# mothership_compact_0_42.net
KiCad netlist of a schematic drawn in EAGLE
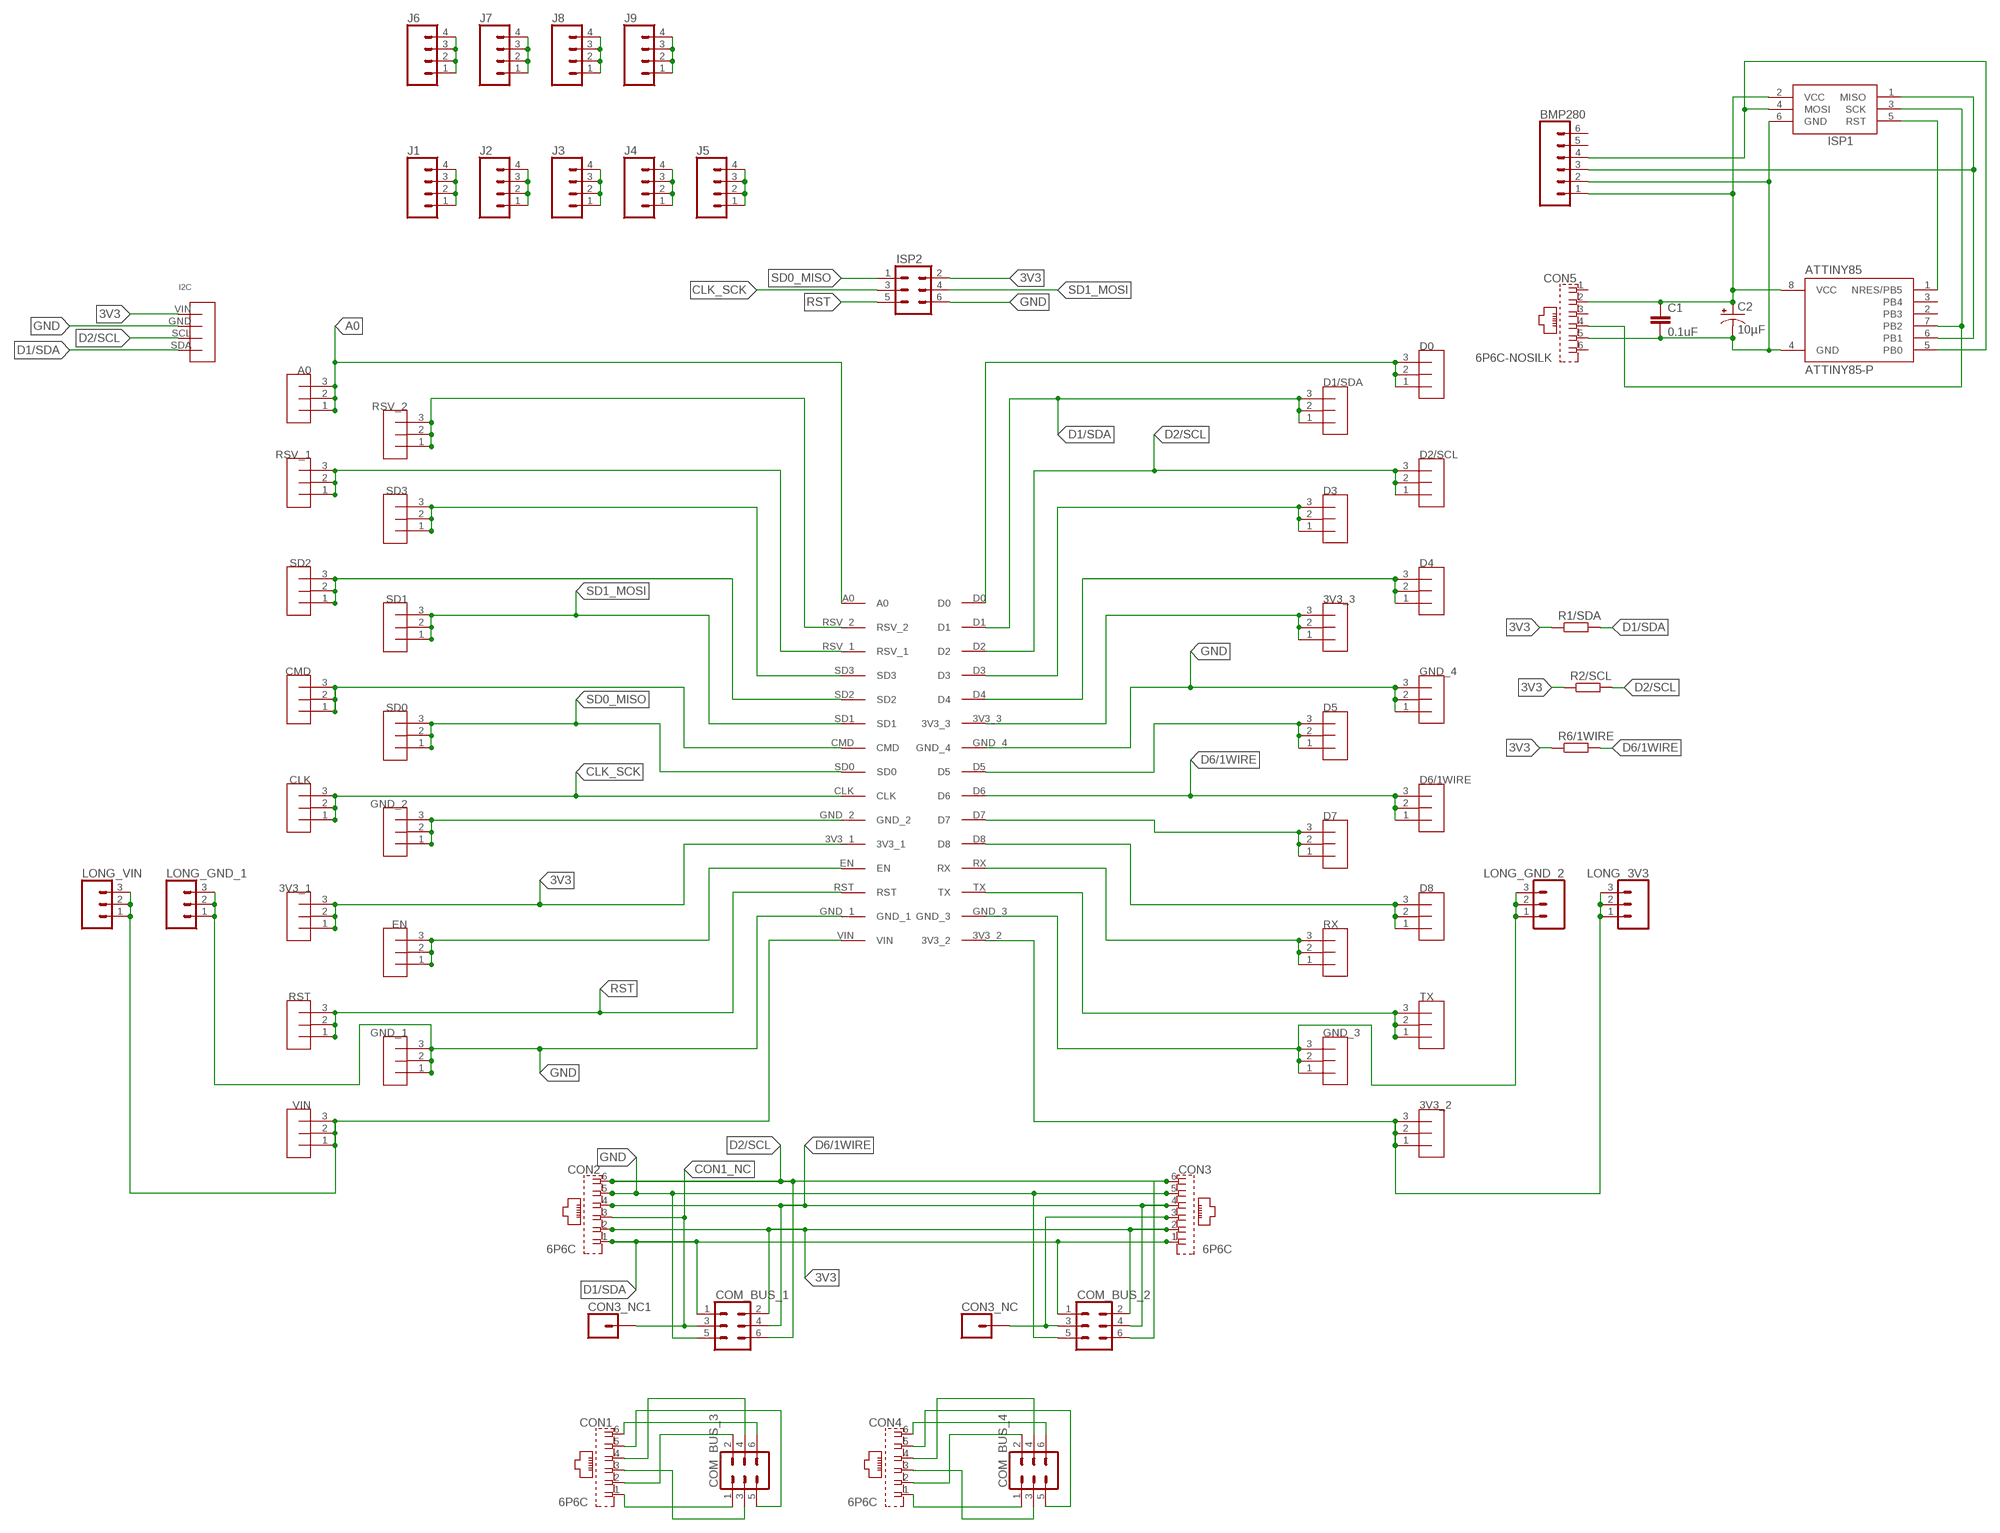
[diagram p0: schematic, sheet 1]

(export (version "E")
  (design (tool "Eeschema 10.0.6"))
  (components
    (comp (ref "3V3_1")
      (value "JUMPERS")
      (footprint "eagle-import:3PIN")
      (libsource (lib "eagle-import") (part "JUMPERS"))
    )
    (comp (ref "3V3_2")
      (value "JUMPERS")
      (footprint "eagle-import:3PIN")
      (libsource (lib "eagle-import") (part "JUMPERS"))
    )
    (comp (ref "3V3_3")
      (value "JUMPERS")
      (footprint "eagle-import:3PIN")
      (libsource (lib "eagle-import") (part "JUMPERS"))
    )
    (comp (ref "A0")
      (value "JUMPERS")
      (footprint "eagle-import:3PIN")
      (libsource (lib "eagle-import") (part "JUMPERS"))
    )
    (comp (ref "ATTINY85")
      (value "ATTINY85-P")
      (footprint "eagle-import:PDIP08_300MIL")
      (libsource (lib "eagle-import") (part "ATTINY85P-"))
    )
    (comp (ref "BMP280")
      (value "CONN_06NO_SILK_NO_POP")
      (footprint "eagle-import:1X06_NO_SILK")
      (libsource (lib "eagle-import") (part "CONN_06NO_SILK_NO_POP"))
    )
    (comp (ref "C1")
      (value "0.1uF")
      (footprint "eagle-import:C050-045X075")
      (libsource (lib "eagle-import") (part "C-EU050-045X075"))
    )
    (comp (ref "C2")
      (value "10µF")
      (footprint "eagle-import:E2,5-5")
      (libsource (lib "eagle-import") (part "CPOL-USE2.5-5"))
    )
    (comp (ref "CLK")
      (value "JUMPERS")
      (footprint "eagle-import:3PIN")
      (libsource (lib "eagle-import") (part "JUMPERS"))
    )
    (comp (ref "CMD")
      (value "JUMPERS")
      (footprint "eagle-import:3PIN")
      (libsource (lib "eagle-import") (part "JUMPERS"))
    )
    (comp (ref "COM_BUS_1")
      (value "CONN_03X2NO_SILK")
      (footprint "eagle-import:2X3-NS")
      (libsource (lib "eagle-import") (part "CONN_03X2NO_SILK"))
    )
    (comp (ref "COM_BUS_2")
      (value "CONN_03X2NO_SILK")
      (footprint "eagle-import:2X3-NS")
      (libsource (lib "eagle-import") (part "CONN_03X2NO_SILK"))
    )
    (comp (ref "COM_BUS_3")
      (value "CONN_03X2NO_SILK")
      (footprint "eagle-import:2X3-NS")
      (libsource (lib "eagle-import") (part "CONN_03X2NO_SILK"))
    )
    (comp (ref "COM_BUS_4")
      (value "CONN_03X2NO_SILK")
      (footprint "eagle-import:2X3-NS")
      (libsource (lib "eagle-import") (part "CONN_03X2NO_SILK"))
    )
    (comp (ref "CON1")
      (value "6P6C")
      (footprint "eagle-import:RJ11-6P6C-NOSHIELD")
      (libsource (lib "eagle-import") (part "6P6C"))
    )
    (comp (ref "CON2")
      (value "6P6C")
      (footprint "eagle-import:RJ11-6P6C-NOSHIELD")
      (libsource (lib "eagle-import") (part "6P6C"))
    )
    (comp (ref "CON3")
      (value "6P6C")
      (footprint "eagle-import:RJ11-6P6C-NOSHIELD")
      (libsource (lib "eagle-import") (part "6P6C"))
    )
    (comp (ref "CON3_NC")
      (value "CONN_01PTH_NO_SILK_YES_STOP")
      (footprint "eagle-import:1X01_NO_SILK")
      (libsource (lib "eagle-import") (part "CONN_01PTH_NO_SILK_YES_STOP"))
    )
    (comp (ref "CON3_NC1")
      (value "CONN_01PTH_NO_SILK_YES_STOP")
      (footprint "eagle-import:1X01_NO_SILK")
      (libsource (lib "eagle-import") (part "CONN_01PTH_NO_SILK_YES_STOP"))
    )
    (comp (ref "CON4")
      (value "6P6C")
      (footprint "eagle-import:RJ11-6P6C-NOSHIELD")
      (libsource (lib "eagle-import") (part "6P6C"))
    )
    (comp (ref "CON5")
      (value "6P6C-NOSILK")
      (footprint "eagle-import:RJ11-6P6C-NOSHIELD-NOSILK")
      (libsource (lib "eagle-import") (part "6P6C-NOSILK"))
    )
    (comp (ref "D0")
      (value "JUMPERS")
      (footprint "eagle-import:3PIN")
      (libsource (lib "eagle-import") (part "JUMPERS"))
    )
    (comp (ref "D1/SDA")
      (value "JUMPERS")
      (footprint "eagle-import:3PIN")
      (libsource (lib "eagle-import") (part "JUMPERS"))
    )
    (comp (ref "D2/SCL")
      (value "JUMPERS")
      (footprint "eagle-import:3PIN")
      (libsource (lib "eagle-import") (part "JUMPERS"))
    )
    (comp (ref "D3")
      (value "JUMPERS")
      (footprint "eagle-import:3PIN")
      (libsource (lib "eagle-import") (part "JUMPERS"))
    )
    (comp (ref "D4")
      (value "JUMPERS")
      (footprint "eagle-import:3PIN")
      (libsource (lib "eagle-import") (part "JUMPERS"))
    )
    (comp (ref "D5")
      (value "JUMPERS")
      (footprint "eagle-import:3PIN")
      (libsource (lib "eagle-import") (part "JUMPERS"))
    )
    (comp (ref "D6/1WIRE")
      (value "JUMPERS")
      (footprint "eagle-import:3PIN")
      (libsource (lib "eagle-import") (part "JUMPERS"))
    )
    (comp (ref "D7")
      (value "JUMPERS")
      (footprint "eagle-import:3PIN")
      (libsource (lib "eagle-import") (part "JUMPERS"))
    )
    (comp (ref "D8")
      (value "JUMPERS")
      (footprint "eagle-import:3PIN")
      (libsource (lib "eagle-import") (part "JUMPERS"))
    )
    (comp (ref "EN")
      (value "JUMPERS")
      (footprint "eagle-import:3PIN")
      (libsource (lib "eagle-import") (part "JUMPERS"))
    )
    (comp (ref "GND_1")
      (value "JUMPERS")
      (footprint "eagle-import:3PIN")
      (libsource (lib "eagle-import") (part "JUMPERS"))
    )
    (comp (ref "GND_2")
      (value "JUMPERS")
      (footprint "eagle-import:3PIN")
      (libsource (lib "eagle-import") (part "JUMPERS"))
    )
    (comp (ref "GND_3")
      (value "JUMPERS")
      (footprint "eagle-import:3PIN")
      (libsource (lib "eagle-import") (part "JUMPERS"))
    )
    (comp (ref "GND_4")
      (value "JUMPERS")
      (footprint "eagle-import:3PIN")
      (libsource (lib "eagle-import") (part "JUMPERS"))
    )
    (comp (ref "ISP1")
      (value "AVRISP-6")
      (footprint "eagle-import:AVRISP")
      (libsource (lib "eagle-import") (part "AVRISP-6"))
    )
    (comp (ref "ISP2")
      (value "CONN_03X2NO_SILK")
      (footprint "eagle-import:2X3-NS")
      (libsource (lib "eagle-import") (part "CONN_03X2NO_SILK"))
    )
    (comp (ref "J1")
      (value "CONN_041X04_NO_SILK")
      (footprint "eagle-import:1X04_NO_SILK")
      (libsource (lib "eagle-import") (part "CONN_041X04_NO_SILK"))
    )
    (comp (ref "J2")
      (value "CONN_041X04_NO_SILK")
      (footprint "eagle-import:1X04_NO_SILK")
      (libsource (lib "eagle-import") (part "CONN_041X04_NO_SILK"))
    )
    (comp (ref "J3")
      (value "CONN_041X04_NO_SILK")
      (footprint "eagle-import:1X04_NO_SILK")
      (libsource (lib "eagle-import") (part "CONN_041X04_NO_SILK"))
    )
    (comp (ref "J4")
      (value "CONN_041X04_NO_SILK")
      (footprint "eagle-import:1X04_NO_SILK")
      (libsource (lib "eagle-import") (part "CONN_041X04_NO_SILK"))
    )
    (comp (ref "J5")
      (value "CONN_041X04_NO_SILK")
      (footprint "eagle-import:1X04_NO_SILK")
      (libsource (lib "eagle-import") (part "CONN_041X04_NO_SILK"))
    )
    (comp (ref "J6")
      (value "CONN_041X04_NO_SILK")
      (footprint "eagle-import:1X04_NO_SILK")
      (libsource (lib "eagle-import") (part "CONN_041X04_NO_SILK"))
    )
    (comp (ref "J7")
      (value "CONN_041X04_NO_SILK")
      (footprint "eagle-import:1X04_NO_SILK")
      (libsource (lib "eagle-import") (part "CONN_041X04_NO_SILK"))
    )
    (comp (ref "J8")
      (value "CONN_041X04_NO_SILK")
      (footprint "eagle-import:1X04_NO_SILK")
      (libsource (lib "eagle-import") (part "CONN_041X04_NO_SILK"))
    )
    (comp (ref "J9")
      (value "CONN_041X04_NO_SILK")
      (footprint "eagle-import:1X04_NO_SILK")
      (libsource (lib "eagle-import") (part "CONN_041X04_NO_SILK"))
    )
    (comp (ref "LONG_3V3")
      (value "CONN_03")
      (footprint "eagle-import:1X03")
      (libsource (lib "eagle-import") (part "CONN_03"))
    )
    (comp (ref "LONG_GND_1")
      (value "CONN_03")
      (footprint "eagle-import:1X03")
      (libsource (lib "eagle-import") (part "CONN_03"))
    )
    (comp (ref "LONG_GND_2")
      (value "CONN_03")
      (footprint "eagle-import:1X03")
      (libsource (lib "eagle-import") (part "CONN_03"))
    )
    (comp (ref "LONG_VIN")
      (value "CONN_03")
      (footprint "eagle-import:1X03")
      (libsource (lib "eagle-import") (part "CONN_03"))
    )
    (comp (ref "R1/SDA")
      (value "R-EU_0207/10")
      (footprint "eagle-import:0207_10")
      (libsource (lib "eagle-import") (part "R-EU_0207/10"))
    )
    (comp (ref "R2/SCL")
      (value "R-EU_0207/10")
      (footprint "eagle-import:0207_10")
      (libsource (lib "eagle-import") (part "R-EU_0207/10"))
    )
    (comp (ref "R6/1WIRE")
      (value "R-EU_0207/10")
      (footprint "eagle-import:0207_10")
      (libsource (lib "eagle-import") (part "R-EU_0207/10"))
    )
    (comp (ref "RST")
      (value "JUMPERS")
      (footprint "eagle-import:3PIN")
      (libsource (lib "eagle-import") (part "JUMPERS"))
    )
    (comp (ref "RSV_1")
      (value "JUMPERS")
      (footprint "eagle-import:3PIN")
      (libsource (lib "eagle-import") (part "JUMPERS"))
    )
    (comp (ref "RSV_2")
      (value "JUMPERS")
      (footprint "eagle-import:3PIN")
      (libsource (lib "eagle-import") (part "JUMPERS"))
    )
    (comp (ref "RX")
      (value "JUMPERS")
      (footprint "eagle-import:3PIN")
      (libsource (lib "eagle-import") (part "JUMPERS"))
    )
    (comp (ref "SD0")
      (value "JUMPERS")
      (footprint "eagle-import:3PIN")
      (libsource (lib "eagle-import") (part "JUMPERS"))
    )
    (comp (ref "SD1")
      (value "JUMPERS")
      (footprint "eagle-import:3PIN")
      (libsource (lib "eagle-import") (part "JUMPERS"))
    )
    (comp (ref "SD2")
      (value "JUMPERS")
      (footprint "eagle-import:3PIN")
      (libsource (lib "eagle-import") (part "JUMPERS"))
    )
    (comp (ref "SD3")
      (value "JUMPERS")
      (footprint "eagle-import:3PIN")
      (libsource (lib "eagle-import") (part "JUMPERS"))
    )
    (comp (ref "TX")
      (value "JUMPERS")
      (footprint "eagle-import:3PIN")
      (libsource (lib "eagle-import") (part "JUMPERS"))
    )
    (comp (ref "U$1")
      (value "NODEMCU")
      (footprint "eagle-import:NODEMCU")
      (libsource (lib "eagle-import") (part "NODEMCU"))
    )
    (comp (ref "U$2")
      (value "I2CJUMPER")
      (footprint "eagle-import:4PIN,NAMED")
      (libsource (lib "eagle-import") (part "I2CJUMPER"))
    )
    (comp (ref "VIN")
      (value "JUMPERS")
      (footprint "eagle-import:3PIN")
      (libsource (lib "eagle-import") (part "JUMPERS"))
    )
  )
  (nets
    (net (code "1") (name "3V3") (class "Default")
      (node (ref "3V3_1") (pin "1") (pinfunction "P$1_1") (pintype "bidirectional"))
      (node (ref "3V3_1") (pin "2") (pinfunction "P$2_2") (pintype "bidirectional"))
      (node (ref "3V3_1") (pin "3") (pinfunction "P$3_3") (pintype "bidirectional"))
      (node (ref "3V3_2") (pin "1") (pinfunction "P$1_1") (pintype "bidirectional"))
      (node (ref "3V3_2") (pin "2") (pinfunction "P$2_2") (pintype "bidirectional"))
      (node (ref "3V3_2") (pin "3") (pinfunction "P$3_3") (pintype "bidirectional"))
      (node (ref "3V3_3") (pin "1") (pinfunction "P$1_1") (pintype "bidirectional"))
      (node (ref "3V3_3") (pin "2") (pinfunction "P$2_2") (pintype "bidirectional"))
      (node (ref "3V3_3") (pin "3") (pinfunction "P$3_3") (pintype "bidirectional"))
      (node (ref "COM_BUS_1") (pin "2") (pinfunction "2_2") (pintype "bidirectional"))
      (node (ref "COM_BUS_2") (pin "2") (pinfunction "2_2") (pintype "bidirectional"))
      (node (ref "CON2") (pin "2") (pinfunction "5_2") (pintype "passive"))
      (node (ref "CON3") (pin "2") (pinfunction "5_2") (pintype "passive"))
      (node (ref "ISP2") (pin "2") (pinfunction "2_2") (pintype "bidirectional"))
      (node (ref "LONG_3V3") (pin "1") (pinfunction "1_1") (pintype "passive"))
      (node (ref "LONG_3V3") (pin "2") (pinfunction "2_2") (pintype "passive"))
      (node (ref "LONG_3V3") (pin "3") (pinfunction "3_3") (pintype "passive"))
      (node (ref "R1/SDA") (pin "1") (pinfunction "1_1") (pintype "passive"))
      (node (ref "R2/SCL") (pin "1") (pinfunction "1_1") (pintype "passive"))
      (node (ref "R6/1WIRE") (pin "1") (pinfunction "1_1") (pintype "passive"))
      (node (ref "U$1") (pin "3V3_1") (pinfunction "3V3_1_3V3_1") (pintype "bidirectional"))
      (node (ref "U$1") (pin "3V3_2") (pinfunction "3V3_2_3V3_2") (pintype "bidirectional"))
      (node (ref "U$1") (pin "3V3_3") (pinfunction "3V3_3_3V3_3") (pintype "bidirectional"))
      (node (ref "U$2") (pin "VIN") (pinfunction "VIN_VIN") (pintype "bidirectional"))
    )
    (net (code "2") (name "A0") (class "Default")
      (node (ref "A0") (pin "1") (pinfunction "P$1_1") (pintype "bidirectional"))
      (node (ref "A0") (pin "2") (pinfunction "P$2_2") (pintype "bidirectional"))
      (node (ref "A0") (pin "3") (pinfunction "P$3_3") (pintype "bidirectional"))
      (node (ref "U$1") (pin "A0") (pinfunction "A0_A0") (pintype "bidirectional"))
    )
    (net (code "3") (name "CLK_SCK") (class "Default")
      (node (ref "CLK") (pin "1") (pinfunction "P$1_1") (pintype "bidirectional"))
      (node (ref "CLK") (pin "2") (pinfunction "P$2_2") (pintype "bidirectional"))
      (node (ref "CLK") (pin "3") (pinfunction "P$3_3") (pintype "bidirectional"))
      (node (ref "ISP2") (pin "3") (pinfunction "3_3") (pintype "bidirectional"))
      (node (ref "U$1") (pin "CLK") (pinfunction "CLK_CLK") (pintype "bidirectional"))
    )
    (net (code "4") (name "CON1_NC") (class "Default")
      (node (ref "COM_BUS_1") (pin "3") (pinfunction "3_3") (pintype "bidirectional"))
      (node (ref "CON2") (pin "3") (pinfunction "4_3") (pintype "passive"))
      (node (ref "CON3_NC1") (pin "1") (pinfunction "1_1") (pintype "passive"))
    )
    (net (code "5") (name "D1{slash}SDA") (class "Default")
      (node (ref "COM_BUS_1") (pin "1") (pinfunction "1_1") (pintype "bidirectional"))
      (node (ref "COM_BUS_2") (pin "1") (pinfunction "1_1") (pintype "bidirectional"))
      (node (ref "CON2") (pin "1") (pinfunction "6_1") (pintype "passive"))
      (node (ref "CON3") (pin "1") (pinfunction "6_1") (pintype "passive"))
      (node (ref "D1/SDA") (pin "1") (pinfunction "P$1_1") (pintype "bidirectional"))
      (node (ref "D1/SDA") (pin "2") (pinfunction "P$2_2") (pintype "bidirectional"))
      (node (ref "D1/SDA") (pin "3") (pinfunction "P$3_3") (pintype "bidirectional"))
      (node (ref "R1/SDA") (pin "2") (pinfunction "2_2") (pintype "passive"))
      (node (ref "U$1") (pin "D1") (pinfunction "D1_D1") (pintype "bidirectional"))
      (node (ref "U$2") (pin "SDA") (pinfunction "SDA_SDA") (pintype "bidirectional"))
    )
    (net (code "6") (name "D2{slash}SCL") (class "Default")
      (node (ref "COM_BUS_1") (pin "6") (pinfunction "6_6") (pintype "bidirectional"))
      (node (ref "COM_BUS_2") (pin "6") (pinfunction "6_6") (pintype "bidirectional"))
      (node (ref "CON2") (pin "6") (pinfunction "1_6") (pintype "passive"))
      (node (ref "CON3") (pin "6") (pinfunction "1_6") (pintype "passive"))
      (node (ref "D2/SCL") (pin "1") (pinfunction "P$1_1") (pintype "bidirectional"))
      (node (ref "D2/SCL") (pin "2") (pinfunction "P$2_2") (pintype "bidirectional"))
      (node (ref "D2/SCL") (pin "3") (pinfunction "P$3_3") (pintype "bidirectional"))
      (node (ref "R2/SCL") (pin "2") (pinfunction "2_2") (pintype "passive"))
      (node (ref "U$1") (pin "D2") (pinfunction "D2_D2") (pintype "bidirectional"))
      (node (ref "U$2") (pin "SCL") (pinfunction "SCL_SCL") (pintype "bidirectional"))
    )
    (net (code "7") (name "D6{slash}1WIRE") (class "Default")
      (node (ref "COM_BUS_1") (pin "4") (pinfunction "4_4") (pintype "bidirectional"))
      (node (ref "COM_BUS_2") (pin "4") (pinfunction "4_4") (pintype "bidirectional"))
      (node (ref "CON2") (pin "4") (pinfunction "3_4") (pintype "passive"))
      (node (ref "CON3") (pin "4") (pinfunction "3_4") (pintype "passive"))
      (node (ref "D6/1WIRE") (pin "1") (pinfunction "P$1_1") (pintype "bidirectional"))
      (node (ref "D6/1WIRE") (pin "2") (pinfunction "P$2_2") (pintype "bidirectional"))
      (node (ref "D6/1WIRE") (pin "3") (pinfunction "P$3_3") (pintype "bidirectional"))
      (node (ref "R6/1WIRE") (pin "2") (pinfunction "2_2") (pintype "passive"))
      (node (ref "U$1") (pin "D6") (pinfunction "D6_D6") (pintype "bidirectional"))
    )
    (net (code "8") (name "GND") (class "Default")
      (node (ref "COM_BUS_1") (pin "5") (pinfunction "5_5") (pintype "bidirectional"))
      (node (ref "COM_BUS_2") (pin "5") (pinfunction "5_5") (pintype "bidirectional"))
      (node (ref "CON2") (pin "5") (pinfunction "2_5") (pintype "passive"))
      (node (ref "CON3") (pin "5") (pinfunction "2_5") (pintype "passive"))
      (node (ref "GND_1") (pin "1") (pinfunction "P$1_1") (pintype "bidirectional"))
      (node (ref "GND_1") (pin "2") (pinfunction "P$2_2") (pintype "bidirectional"))
      (node (ref "GND_1") (pin "3") (pinfunction "P$3_3") (pintype "bidirectional"))
      (node (ref "GND_2") (pin "1") (pinfunction "P$1_1") (pintype "bidirectional"))
      (node (ref "GND_2") (pin "2") (pinfunction "P$2_2") (pintype "bidirectional"))
      (node (ref "GND_2") (pin "3") (pinfunction "P$3_3") (pintype "bidirectional"))
      (node (ref "GND_3") (pin "1") (pinfunction "P$1_1") (pintype "bidirectional"))
      (node (ref "GND_3") (pin "2") (pinfunction "P$2_2") (pintype "bidirectional"))
      (node (ref "GND_3") (pin "3") (pinfunction "P$3_3") (pintype "bidirectional"))
      (node (ref "GND_4") (pin "1") (pinfunction "P$1_1") (pintype "bidirectional"))
      (node (ref "GND_4") (pin "2") (pinfunction "P$2_2") (pintype "bidirectional"))
      (node (ref "GND_4") (pin "3") (pinfunction "P$3_3") (pintype "bidirectional"))
      (node (ref "ISP2") (pin "6") (pinfunction "6_6") (pintype "bidirectional"))
      (node (ref "LONG_GND_1") (pin "1") (pinfunction "1_1") (pintype "passive"))
      (node (ref "LONG_GND_1") (pin "2") (pinfunction "2_2") (pintype "passive"))
      (node (ref "LONG_GND_1") (pin "3") (pinfunction "3_3") (pintype "passive"))
      (node (ref "LONG_GND_2") (pin "1") (pinfunction "1_1") (pintype "passive"))
      (node (ref "LONG_GND_2") (pin "2") (pinfunction "2_2") (pintype "passive"))
      (node (ref "LONG_GND_2") (pin "3") (pinfunction "3_3") (pintype "passive"))
      (node (ref "U$1") (pin "GND_1") (pinfunction "GND_1_GND_1") (pintype "bidirectional"))
      (node (ref "U$1") (pin "GND_2") (pinfunction "GND_2_GND_2") (pintype "bidirectional"))
      (node (ref "U$1") (pin "GND_3") (pinfunction "GND_3_GND_3") (pintype "bidirectional"))
      (node (ref "U$1") (pin "GND_4") (pinfunction "GND_4_GND_4") (pintype "bidirectional"))
      (node (ref "U$2") (pin "GND") (pinfunction "GND_GND") (pintype "bidirectional"))
    )
    (net (code "9") (name "Net-(ATTINY85-GND)") (class "Default")
      (node (ref "ATTINY85") (pin "4") (pinfunction "GND_4") (pintype "power_in"))
      (node (ref "BMP280") (pin "2") (pinfunction "2_2") (pintype "passive"))
      (node (ref "C1") (pin "2") (pinfunction "2_2") (pintype "passive"))
      (node (ref "C2") (pin "-") (pinfunction "-_-") (pintype "passive"))
      (node (ref "CON5") (pin "5") (pinfunction "5_5") (pintype "passive"))
      (node (ref "ISP1") (pin "6") (pinfunction "GND_6") (pintype "power_in"))
    )
    (net (code "10") (name "Net-(ATTINY85-NRES{slash}PB5)") (class "Default")
      (node (ref "ATTINY85") (pin "1") (pinfunction "NRES/PB5_1") (pintype "bidirectional"))
      (node (ref "ISP1") (pin "5") (pinfunction "RST_5") (pintype "output"))
    )
    (net (code "11") (name "Net-(ATTINY85-PB0)") (class "Default")
      (node (ref "ATTINY85") (pin "5") (pinfunction "PB0_5") (pintype "bidirectional"))
      (node (ref "BMP280") (pin "4") (pinfunction "4_4") (pintype "passive"))
      (node (ref "ISP1") (pin "4") (pinfunction "MOSI_4") (pintype "output"))
    )
    (net (code "12") (name "Net-(ATTINY85-PB1)") (class "Default")
      (node (ref "ATTINY85") (pin "6") (pinfunction "PB1_6") (pintype "bidirectional"))
      (node (ref "BMP280") (pin "3") (pinfunction "3_3") (pintype "passive"))
      (node (ref "ISP1") (pin "1") (pinfunction "MISO_1") (pintype "input"))
    )
    (net (code "13") (name "Net-(ATTINY85-PB2)") (class "Default")
      (node (ref "ATTINY85") (pin "7") (pinfunction "PB2_7") (pintype "bidirectional"))
      (node (ref "CON5") (pin "4") (pinfunction "4_4") (pintype "passive"))
      (node (ref "ISP1") (pin "3") (pinfunction "SCK_3") (pintype "output"))
    )
    (net (code "14") (name "Net-(ATTINY85-VCC)") (class "Default")
      (node (ref "ATTINY85") (pin "8") (pinfunction "VCC_8") (pintype "power_in"))
      (node (ref "BMP280") (pin "1") (pinfunction "1_1") (pintype "passive"))
      (node (ref "C1") (pin "1") (pinfunction "1_1") (pintype "passive"))
      (node (ref "C2") (pin "+") (pinfunction "+_+") (pintype "passive"))
      (node (ref "CON5") (pin "2") (pinfunction "2_2") (pintype "passive"))
      (node (ref "ISP1") (pin "2") (pinfunction "VCC_2") (pintype "power_in"))
    )
    (net (code "15") (name "Net-(CMD-P$1)") (class "Default")
      (node (ref "CMD") (pin "1") (pinfunction "P$1_1") (pintype "bidirectional"))
      (node (ref "CMD") (pin "2") (pinfunction "P$2_2") (pintype "bidirectional"))
      (node (ref "CMD") (pin "3") (pinfunction "P$3_3") (pintype "bidirectional"))
      (node (ref "U$1") (pin "CMD") (pinfunction "CMD_CMD") (pintype "bidirectional"))
    )
    (net (code "16") (name "Net-(CON1-1)") (class "Default")
      (node (ref "COM_BUS_3") (pin "6") (pinfunction "6_6") (pintype "bidirectional"))
      (node (ref "CON1") (pin "6") (pinfunction "1_6") (pintype "passive"))
    )
    (net (code "17") (name "Net-(CON1-2)") (class "Default")
      (node (ref "COM_BUS_3") (pin "5") (pinfunction "5_5") (pintype "bidirectional"))
      (node (ref "CON1") (pin "5") (pinfunction "2_5") (pintype "passive"))
    )
    (net (code "18") (name "Net-(CON1-3)") (class "Default")
      (node (ref "COM_BUS_3") (pin "4") (pinfunction "4_4") (pintype "bidirectional"))
      (node (ref "CON1") (pin "4") (pinfunction "3_4") (pintype "passive"))
    )
    (net (code "19") (name "Net-(CON1-4)") (class "Default")
      (node (ref "COM_BUS_3") (pin "3") (pinfunction "3_3") (pintype "bidirectional"))
      (node (ref "CON1") (pin "3") (pinfunction "4_3") (pintype "passive"))
    )
    (net (code "20") (name "Net-(CON1-5)") (class "Default")
      (node (ref "COM_BUS_3") (pin "2") (pinfunction "2_2") (pintype "bidirectional"))
      (node (ref "CON1") (pin "2") (pinfunction "5_2") (pintype "passive"))
    )
    (net (code "21") (name "Net-(CON1-6)") (class "Default")
      (node (ref "COM_BUS_3") (pin "1") (pinfunction "1_1") (pintype "bidirectional"))
      (node (ref "CON1") (pin "1") (pinfunction "6_1") (pintype "passive"))
    )
    (net (code "22") (name "Net-(CON3-4)") (class "Default")
      (node (ref "COM_BUS_2") (pin "3") (pinfunction "3_3") (pintype "bidirectional"))
      (node (ref "CON3") (pin "3") (pinfunction "4_3") (pintype "passive"))
      (node (ref "CON3_NC") (pin "1") (pinfunction "1_1") (pintype "passive"))
    )
    (net (code "23") (name "Net-(CON4-1)") (class "Default")
      (node (ref "COM_BUS_4") (pin "6") (pinfunction "6_6") (pintype "bidirectional"))
      (node (ref "CON4") (pin "6") (pinfunction "1_6") (pintype "passive"))
    )
    (net (code "24") (name "Net-(CON4-2)") (class "Default")
      (node (ref "COM_BUS_4") (pin "5") (pinfunction "5_5") (pintype "bidirectional"))
      (node (ref "CON4") (pin "5") (pinfunction "2_5") (pintype "passive"))
    )
    (net (code "25") (name "Net-(CON4-3)") (class "Default")
      (node (ref "COM_BUS_4") (pin "4") (pinfunction "4_4") (pintype "bidirectional"))
      (node (ref "CON4") (pin "4") (pinfunction "3_4") (pintype "passive"))
    )
    (net (code "26") (name "Net-(CON4-4)") (class "Default")
      (node (ref "COM_BUS_4") (pin "3") (pinfunction "3_3") (pintype "bidirectional"))
      (node (ref "CON4") (pin "3") (pinfunction "4_3") (pintype "passive"))
    )
    (net (code "27") (name "Net-(CON4-5)") (class "Default")
      (node (ref "COM_BUS_4") (pin "2") (pinfunction "2_2") (pintype "bidirectional"))
      (node (ref "CON4") (pin "2") (pinfunction "5_2") (pintype "passive"))
    )
    (net (code "28") (name "Net-(CON4-6)") (class "Default")
      (node (ref "COM_BUS_4") (pin "1") (pinfunction "1_1") (pintype "bidirectional"))
      (node (ref "CON4") (pin "1") (pinfunction "6_1") (pintype "passive"))
    )
    (net (code "29") (name "Net-(D0-P$1)") (class "Default")
      (node (ref "D0") (pin "1") (pinfunction "P$1_1") (pintype "bidirectional"))
      (node (ref "D0") (pin "2") (pinfunction "P$2_2") (pintype "bidirectional"))
      (node (ref "D0") (pin "3") (pinfunction "P$3_3") (pintype "bidirectional"))
      (node (ref "U$1") (pin "D0") (pinfunction "D0_D0") (pintype "bidirectional"))
    )
    (net (code "30") (name "Net-(D3-P$1)") (class "Default")
      (node (ref "D3") (pin "1") (pinfunction "P$1_1") (pintype "bidirectional"))
      (node (ref "D3") (pin "2") (pinfunction "P$2_2") (pintype "bidirectional"))
      (node (ref "D3") (pin "3") (pinfunction "P$3_3") (pintype "bidirectional"))
      (node (ref "U$1") (pin "D3") (pinfunction "D3_D3") (pintype "bidirectional"))
    )
    (net (code "31") (name "Net-(D4-P$1)") (class "Default")
      (node (ref "D4") (pin "1") (pinfunction "P$1_1") (pintype "bidirectional"))
      (node (ref "D4") (pin "2") (pinfunction "P$2_2") (pintype "bidirectional"))
      (node (ref "D4") (pin "3") (pinfunction "P$3_3") (pintype "bidirectional"))
      (node (ref "U$1") (pin "D4") (pinfunction "D4_D4") (pintype "bidirectional"))
    )
    (net (code "32") (name "Net-(D5-P$1)") (class "Default")
      (node (ref "D5") (pin "1") (pinfunction "P$1_1") (pintype "bidirectional"))
      (node (ref "D5") (pin "2") (pinfunction "P$2_2") (pintype "bidirectional"))
      (node (ref "D5") (pin "3") (pinfunction "P$3_3") (pintype "bidirectional"))
      (node (ref "U$1") (pin "D5") (pinfunction "D5_D5") (pintype "bidirectional"))
    )
    (net (code "33") (name "Net-(D7-P$1)") (class "Default")
      (node (ref "D7") (pin "1") (pinfunction "P$1_1") (pintype "bidirectional"))
      (node (ref "D7") (pin "2") (pinfunction "P$2_2") (pintype "bidirectional"))
      (node (ref "D7") (pin "3") (pinfunction "P$3_3") (pintype "bidirectional"))
      (node (ref "U$1") (pin "D7") (pinfunction "D7_D7") (pintype "bidirectional"))
    )
    (net (code "34") (name "Net-(D8-P$1)") (class "Default")
      (node (ref "D8") (pin "1") (pinfunction "P$1_1") (pintype "bidirectional"))
      (node (ref "D8") (pin "2") (pinfunction "P$2_2") (pintype "bidirectional"))
      (node (ref "D8") (pin "3") (pinfunction "P$3_3") (pintype "bidirectional"))
      (node (ref "U$1") (pin "D8") (pinfunction "D8_D8") (pintype "bidirectional"))
    )
    (net (code "35") (name "Net-(EN-P$1)") (class "Default")
      (node (ref "EN") (pin "1") (pinfunction "P$1_1") (pintype "bidirectional"))
      (node (ref "EN") (pin "2") (pinfunction "P$2_2") (pintype "bidirectional"))
      (node (ref "EN") (pin "3") (pinfunction "P$3_3") (pintype "bidirectional"))
      (node (ref "U$1") (pin "EN") (pinfunction "EN_EN") (pintype "bidirectional"))
    )
    (net (code "36") (name "Net-(J1-Pad1)") (class "Default")
      (node (ref "J1") (pin "1") (pinfunction "1_1") (pintype "passive"))
      (node (ref "J1") (pin "2") (pinfunction "2_2") (pintype "passive"))
      (node (ref "J1") (pin "3") (pinfunction "3_3") (pintype "passive"))
      (node (ref "J1") (pin "4") (pinfunction "4_4") (pintype "passive"))
    )
    (net (code "37") (name "Net-(J2-Pad1)") (class "Default")
      (node (ref "J2") (pin "1") (pinfunction "1_1") (pintype "passive"))
      (node (ref "J2") (pin "2") (pinfunction "2_2") (pintype "passive"))
      (node (ref "J2") (pin "3") (pinfunction "3_3") (pintype "passive"))
      (node (ref "J2") (pin "4") (pinfunction "4_4") (pintype "passive"))
    )
    (net (code "38") (name "Net-(J3-Pad1)") (class "Default")
      (node (ref "J3") (pin "1") (pinfunction "1_1") (pintype "passive"))
      (node (ref "J3") (pin "2") (pinfunction "2_2") (pintype "passive"))
      (node (ref "J3") (pin "3") (pinfunction "3_3") (pintype "passive"))
      (node (ref "J3") (pin "4") (pinfunction "4_4") (pintype "passive"))
    )
    (net (code "39") (name "Net-(J4-Pad1)") (class "Default")
      (node (ref "J4") (pin "1") (pinfunction "1_1") (pintype "passive"))
      (node (ref "J4") (pin "2") (pinfunction "2_2") (pintype "passive"))
      (node (ref "J4") (pin "3") (pinfunction "3_3") (pintype "passive"))
      (node (ref "J4") (pin "4") (pinfunction "4_4") (pintype "passive"))
    )
    (net (code "40") (name "Net-(J5-Pad1)") (class "Default")
      (node (ref "J5") (pin "1") (pinfunction "1_1") (pintype "passive"))
      (node (ref "J5") (pin "2") (pinfunction "2_2") (pintype "passive"))
      (node (ref "J5") (pin "3") (pinfunction "3_3") (pintype "passive"))
      (node (ref "J5") (pin "4") (pinfunction "4_4") (pintype "passive"))
    )
    (net (code "41") (name "Net-(J6-Pad1)") (class "Default")
      (node (ref "J6") (pin "1") (pinfunction "1_1") (pintype "passive"))
      (node (ref "J6") (pin "2") (pinfunction "2_2") (pintype "passive"))
      (node (ref "J6") (pin "3") (pinfunction "3_3") (pintype "passive"))
      (node (ref "J6") (pin "4") (pinfunction "4_4") (pintype "passive"))
    )
    (net (code "42") (name "Net-(J7-Pad1)") (class "Default")
      (node (ref "J7") (pin "1") (pinfunction "1_1") (pintype "passive"))
      (node (ref "J7") (pin "2") (pinfunction "2_2") (pintype "passive"))
      (node (ref "J7") (pin "3") (pinfunction "3_3") (pintype "passive"))
      (node (ref "J7") (pin "4") (pinfunction "4_4") (pintype "passive"))
    )
    (net (code "43") (name "Net-(J8-Pad1)") (class "Default")
      (node (ref "J8") (pin "1") (pinfunction "1_1") (pintype "passive"))
      (node (ref "J8") (pin "2") (pinfunction "2_2") (pintype "passive"))
      (node (ref "J8") (pin "3") (pinfunction "3_3") (pintype "passive"))
      (node (ref "J8") (pin "4") (pinfunction "4_4") (pintype "passive"))
    )
    (net (code "44") (name "Net-(J9-Pad1)") (class "Default")
      (node (ref "J9") (pin "1") (pinfunction "1_1") (pintype "passive"))
      (node (ref "J9") (pin "2") (pinfunction "2_2") (pintype "passive"))
      (node (ref "J9") (pin "3") (pinfunction "3_3") (pintype "passive"))
      (node (ref "J9") (pin "4") (pinfunction "4_4") (pintype "passive"))
    )
    (net (code "45") (name "Net-(RSV_1-P$1)") (class "Default")
      (node (ref "RSV_1") (pin "1") (pinfunction "P$1_1") (pintype "bidirectional"))
      (node (ref "RSV_1") (pin "2") (pinfunction "P$2_2") (pintype "bidirectional"))
      (node (ref "RSV_1") (pin "3") (pinfunction "P$3_3") (pintype "bidirectional"))
      (node (ref "U$1") (pin "RSV_1") (pinfunction "RSV_1_RSV_1") (pintype "bidirectional"))
    )
    (net (code "46") (name "Net-(RSV_2-P$1)") (class "Default")
      (node (ref "RSV_2") (pin "1") (pinfunction "P$1_1") (pintype "bidirectional"))
      (node (ref "RSV_2") (pin "2") (pinfunction "P$2_2") (pintype "bidirectional"))
      (node (ref "RSV_2") (pin "3") (pinfunction "P$3_3") (pintype "bidirectional"))
      (node (ref "U$1") (pin "RSV_2") (pinfunction "RSV_2_RSV_2") (pintype "bidirectional"))
    )
    (net (code "47") (name "Net-(RX-P$1)") (class "Default")
      (node (ref "RX") (pin "1") (pinfunction "P$1_1") (pintype "bidirectional"))
      (node (ref "RX") (pin "2") (pinfunction "P$2_2") (pintype "bidirectional"))
      (node (ref "RX") (pin "3") (pinfunction "P$3_3") (pintype "bidirectional"))
      (node (ref "U$1") (pin "RX") (pinfunction "RX_RX") (pintype "bidirectional"))
    )
    (net (code "48") (name "Net-(SD2-P$1)") (class "Default")
      (node (ref "SD2") (pin "1") (pinfunction "P$1_1") (pintype "bidirectional"))
      (node (ref "SD2") (pin "2") (pinfunction "P$2_2") (pintype "bidirectional"))
      (node (ref "SD2") (pin "3") (pinfunction "P$3_3") (pintype "bidirectional"))
      (node (ref "U$1") (pin "SD2") (pinfunction "SD2_SD2") (pintype "bidirectional"))
    )
    (net (code "49") (name "Net-(SD3-P$1)") (class "Default")
      (node (ref "SD3") (pin "1") (pinfunction "P$1_1") (pintype "bidirectional"))
      (node (ref "SD3") (pin "2") (pinfunction "P$2_2") (pintype "bidirectional"))
      (node (ref "SD3") (pin "3") (pinfunction "P$3_3") (pintype "bidirectional"))
      (node (ref "U$1") (pin "SD3") (pinfunction "SD3_SD3") (pintype "bidirectional"))
    )
    (net (code "50") (name "Net-(TX-P$1)") (class "Default")
      (node (ref "TX") (pin "1") (pinfunction "P$1_1") (pintype "bidirectional"))
      (node (ref "TX") (pin "2") (pinfunction "P$2_2") (pintype "bidirectional"))
      (node (ref "TX") (pin "3") (pinfunction "P$3_3") (pintype "bidirectional"))
      (node (ref "U$1") (pin "TX") (pinfunction "TX_TX") (pintype "bidirectional"))
    )
    (net (code "51") (name "Net-(VIN-P$1)") (class "Default")
      (node (ref "LONG_VIN") (pin "1") (pinfunction "1_1") (pintype "passive"))
      (node (ref "LONG_VIN") (pin "2") (pinfunction "2_2") (pintype "passive"))
      (node (ref "LONG_VIN") (pin "3") (pinfunction "3_3") (pintype "passive"))
      (node (ref "U$1") (pin "VIN") (pinfunction "VIN_VIN") (pintype "bidirectional"))
      (node (ref "VIN") (pin "1") (pinfunction "P$1_1") (pintype "bidirectional"))
      (node (ref "VIN") (pin "2") (pinfunction "P$2_2") (pintype "bidirectional"))
      (node (ref "VIN") (pin "3") (pinfunction "P$3_3") (pintype "bidirectional"))
    )
    (net (code "52") (name "RST") (class "Default")
      (node (ref "ISP2") (pin "5") (pinfunction "5_5") (pintype "bidirectional"))
      (node (ref "RST") (pin "1") (pinfunction "P$1_1") (pintype "bidirectional"))
      (node (ref "RST") (pin "2") (pinfunction "P$2_2") (pintype "bidirectional"))
      (node (ref "RST") (pin "3") (pinfunction "P$3_3") (pintype "bidirectional"))
      (node (ref "U$1") (pin "RST") (pinfunction "RST_RST") (pintype "bidirectional"))
    )
    (net (code "53") (name "SD0_MISO") (class "Default")
      (node (ref "ISP2") (pin "1") (pinfunction "1_1") (pintype "bidirectional"))
      (node (ref "SD0") (pin "1") (pinfunction "P$1_1") (pintype "bidirectional"))
      (node (ref "SD0") (pin "2") (pinfunction "P$2_2") (pintype "bidirectional"))
      (node (ref "SD0") (pin "3") (pinfunction "P$3_3") (pintype "bidirectional"))
      (node (ref "U$1") (pin "SD0") (pinfunction "SD0_SD0") (pintype "bidirectional"))
    )
    (net (code "54") (name "SD1_MOSI") (class "Default")
      (node (ref "ISP2") (pin "4") (pinfunction "4_4") (pintype "bidirectional"))
      (node (ref "SD1") (pin "1") (pinfunction "P$1_1") (pintype "bidirectional"))
      (node (ref "SD1") (pin "2") (pinfunction "P$2_2") (pintype "bidirectional"))
      (node (ref "SD1") (pin "3") (pinfunction "P$3_3") (pintype "bidirectional"))
      (node (ref "U$1") (pin "SD1") (pinfunction "SD1_SD1") (pintype "bidirectional"))
    )
    (net (code "55") (name "unconnected-(ATTINY85-PB3-Pad2)") (class "Default")
      (node (ref "ATTINY85") (pin "2") (pinfunction "PB3_2") (pintype "bidirectional"))
    )
    (net (code "56") (name "unconnected-(ATTINY85-PB4-Pad3)") (class "Default")
      (node (ref "ATTINY85") (pin "3") (pinfunction "PB4_3") (pintype "bidirectional"))
    )
    (net (code "57") (name "unconnected-(BMP280-Pad5)") (class "Default")
      (node (ref "BMP280") (pin "5") (pinfunction "5_5") (pintype "passive"))
    )
    (net (code "58") (name "unconnected-(BMP280-Pad6)") (class "Default")
      (node (ref "BMP280") (pin "6") (pinfunction "6_6") (pintype "passive"))
    )
    (net (code "59") (name "unconnected-(CON5-Pad1)") (class "Default")
      (node (ref "CON5") (pin "1") (pinfunction "1_1") (pintype "passive"))
    )
    (net (code "60") (name "unconnected-(CON5-Pad3)") (class "Default")
      (node (ref "CON5") (pin "3") (pinfunction "3_3") (pintype "passive"))
    )
    (net (code "61") (name "unconnected-(CON5-Pad6)") (class "Default")
      (node (ref "CON5") (pin "6") (pinfunction "6_6") (pintype "passive"))
    )
  )
)
